# 12V_Supply.net
KiCad netlist of a schematic drawn in Altium Designer
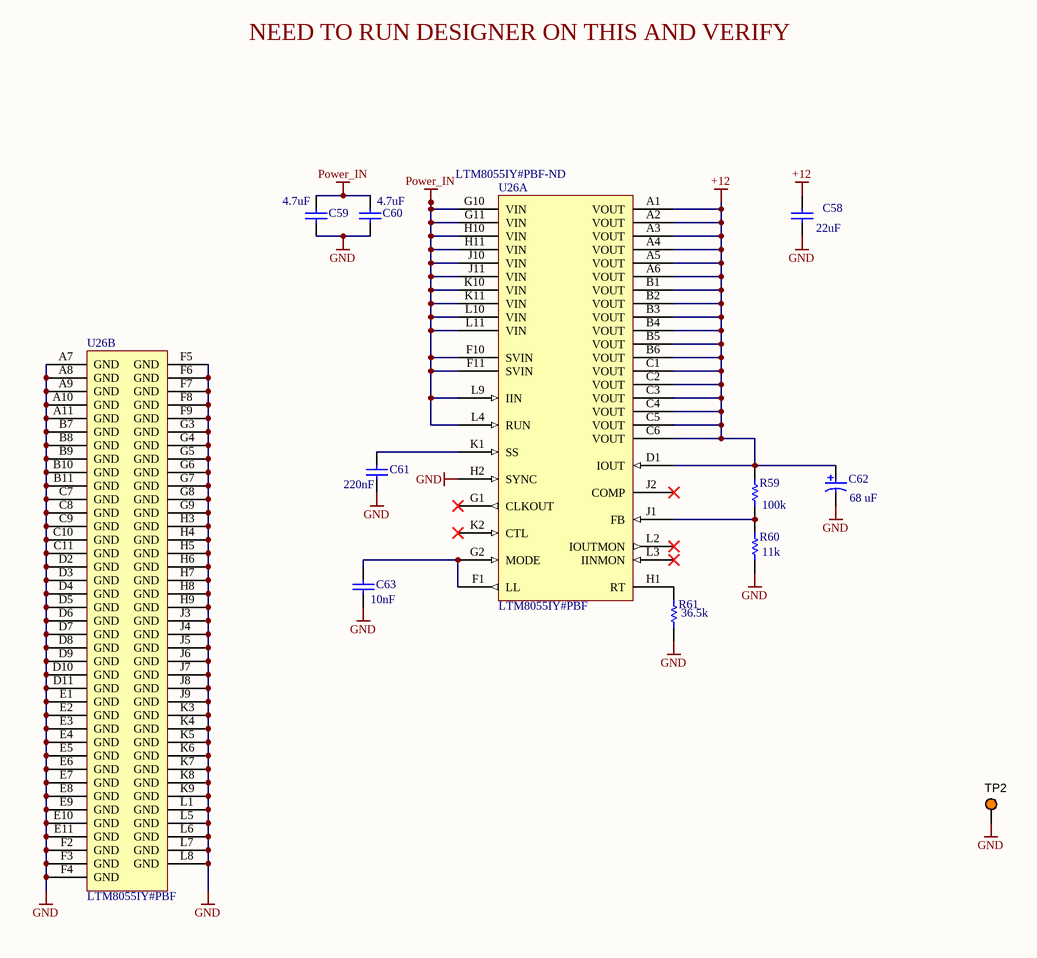
[diagram p0: 12V_Supply.SchDoc]

(export (version "E")
  (design (tool "Eeschema 10.0.6"))
  (components
    (comp (ref "C58")
      (value "CAP CER 1UF 25V X7R 0805")
      (footprint "CAPC0805(2012)155_L")
      (description "22uF 25V X7R 20% 0805")
      (fields
        (field (name "CAPACITANCE") "22uF")
        (field (name "MANUFACTURER") "Kyocera AVX")
        (field (name "MANUFACTURER PART NUMBER") "08053C105JAT2A")
      )
      (libsource (lib "Altium Content Vault") (part "CMP-1036-04882-1"))
    )
    (comp (ref "C59")
      (value "C1210C475K5RACTU")
      (footprint "CAPC3225X280X50LL20T25")
      (description "Chip Capacitor, 4.7 uF, +/- 10%, 50 V, -55 to 125 degC, 1210 (3225 Metric), RoHS, Tape and Reel")
      (fields
        (field (name "VOLTAGE") "50V")
        (field (name "MANUFACTURER") "Kemet")
        (field (name "CAPACITANCE") "4.7uF")
      )
      (libsource (lib "Altium Content Vault") (part "CMP-2000-07550-1"))
    )
    (comp (ref "C60")
      (value "C1210C475K5RACTU")
      (footprint "CAPC3225X280X50LL20T25")
      (description "Chip Capacitor, 4.7 uF, +/- 10%, 50 V, -55 to 125 degC, 1210 (3225 Metric), RoHS, Tape and Reel")
      (fields
        (field (name "VOLTAGE") "50V")
        (field (name "MANUFACTURER") "Kemet")
        (field (name "CAPACITANCE") "4.7uF")
      )
      (libsource (lib "Altium Content Vault") (part "CMP-2000-07550-1"))
    )
    (comp (ref "C61")
      (value "GRM155R71C224KA12D")
      (footprint "CAPC0402(1005)60_M")
      (description "0.22µF ±10% 16V Ceramic Capacitor X7R 0402 (1005 Metric)")
      (fields
        (field (name "TOLERANCE") "Â±10%")
        (field (name "MANUFACTURER") "Murata")
        (field (name "CAPACITANCE") "220nF")
      )
      (libsource (lib "Altium Content Vault") (part "CAP"))
    )
    (comp (ref "C62")
      (value "UUD1E680MCL1GS")
      (footprint "NIC-CAPA2-6.3X5.8_V")
      (fields (field (name "RATED CAPACITANCE") "68 uF") (field (name "MANUFACTURER") "Nichicon"))
      (libsource (lib "Altium Content Vault") (part "NIC-CAP-P-2"))
    )
    (comp (ref "C63")
      (value "0402YC103KAT2A")
      (footprint "CAPC1005X56X25NL10T15")
      (description "10000pF ±10% 16V Ceramic Capacitor X7R 0402 (1005 Metric)")
      (fields
        (field (name "MANUFACTURER") "AVX Interconnect / Elco")
        (field (name "CAPACITANCE") "10nF")
        (field (name "TOLERANCE") "10%")
      )
      (libsource (lib "Altium Content Vault") (part "CAP"))
    )
    (comp (ref "R59")
      (value "CRCW0603100KFKEA")
      (footprint "RESC1609X50X30LL10T20")
      (description "100 kOhms ±1% 0.1W, 1/10W Chip Resistor 0603 (1608 Metric) Automotive AEC-Q200 Thick Film")
      (fields
        (field (name "MANUFACTURER") "Vishay Dale")
        (field (name "MANUFACTURER PART NUMBER") "CRCW0603-100KFKEA")
        (field (name "RESISTANCE") "100k")
      )
      (libsource (lib "Altium Content Vault") (part "RES"))
    )
    (comp (ref "R60")
      (value "CRCW060311K0FKEA")
      (footprint "RESC1609X50X30ML10T20")
      (description "11 kOhms ±1% 0.1W, 1/10W Chip Resistor 0603 (1608 Metric) Automotive AEC-Q200 Thick Film")
      (fields
        (field (name "MANUFACTURER") "Vishay Dale")
        (field (name "RESISTANCE") "11k")
        (field (name "TOLERANCE") "1%")
      )
      (libsource (lib "Altium Content Vault") (part "RES"))
    )
    (comp (ref "R61")
      (value "CRCW080536K5FKEA")
      (footprint "RESC0805(2012)_L")
      (description "36.5 kOhms ±1% 0.125W, 1/8W Chip Resistor 0805 (2012 Metric) Automotive AEC-Q200 Thick Film")
      (fields
        (field (name "POWER") "0.125 W")
        (field (name "TOLERANCE") "1 %")
        (field (name "RESISTANCE") "36.5k")
      )
      (libsource (lib "Altium Content Vault") (part "RES"))
    )
    (comp (ref "TP2")
      (value "5003")
      (footprint "KSTN-5003")
      (description "Test Point, Orange, 1-Pin THD, RoHS")
      (libsource (lib "Altium Content Vault") (part "CMP-1672-00009-1"))
    )
    (comp (ref "U26")
      (value "LTM8055IY#PBF")
      (footprint "LT-BGA-121-15000X15000X4920")
      (description "Buck-Boost uModule Regulator, 8.5 A, 5 to 36 V, -40 to 125 degC, 121-Ball BGA, RoHS, Tray")
      (fields
        (field (name "MANUFACTURER") "LinearTechnology")
        (field (name "SUPPLIER PART NUMBER 1") "LTM8055IY#PBF-ND")
      )
      (libsource (lib "Altium Content Vault") (part "LT-LTM8055-BGA-121"))
    )
  )
  (nets
    (net (code "1") (name "+12") (class "Default")
      (node (ref "C58") (pin "2") (pinfunction "2_2") (pintype "passive"))
      (node (ref "C62") (pin "1") (pinfunction "1_1") (pintype "passive"))
      (node (ref "R59") (pin "2") (pinfunction "2_2") (pintype "passive"))
      (node (ref "U26") (pin "A1") (pinfunction "VOUT_A1") (pintype "power_in"))
      (node (ref "U26") (pin "A2") (pinfunction "VOUT_A2") (pintype "power_in"))
      (node (ref "U26") (pin "A3") (pinfunction "VOUT_A3") (pintype "power_in"))
      (node (ref "U26") (pin "A4") (pinfunction "VOUT_A4") (pintype "power_in"))
      (node (ref "U26") (pin "A5") (pinfunction "VOUT_A5") (pintype "power_in"))
      (node (ref "U26") (pin "A6") (pinfunction "VOUT_A6") (pintype "power_in"))
      (node (ref "U26") (pin "B1") (pinfunction "VOUT_B1") (pintype "power_in"))
      (node (ref "U26") (pin "B2") (pinfunction "VOUT_B2") (pintype "power_in"))
      (node (ref "U26") (pin "B3") (pinfunction "VOUT_B3") (pintype "power_in"))
      (node (ref "U26") (pin "B4") (pinfunction "VOUT_B4") (pintype "power_in"))
      (node (ref "U26") (pin "B5") (pinfunction "VOUT_B5") (pintype "power_in"))
      (node (ref "U26") (pin "B6") (pinfunction "VOUT_B6") (pintype "power_in"))
      (node (ref "U26") (pin "C1") (pinfunction "VOUT_C1") (pintype "power_in"))
      (node (ref "U26") (pin "C2") (pinfunction "VOUT_C2") (pintype "power_in"))
      (node (ref "U26") (pin "C3") (pinfunction "VOUT_C3") (pintype "power_in"))
      (node (ref "U26") (pin "C4") (pinfunction "VOUT_C4") (pintype "power_in"))
      (node (ref "U26") (pin "C5") (pinfunction "VOUT_C5") (pintype "power_in"))
      (node (ref "U26") (pin "C6") (pinfunction "VOUT_C6") (pintype "power_in"))
      (node (ref "U26") (pin "D1") (pinfunction "IOUT_D1") (pintype "input"))
    )
    (net (code "2") (name "GND") (class "Default")
      (node (ref "C58") (pin "1") (pinfunction "1_1") (pintype "passive"))
      (node (ref "C59") (pin "1") (pinfunction "1_1") (pintype "passive"))
      (node (ref "C60") (pin "1") (pinfunction "1_1") (pintype "passive"))
      (node (ref "C61") (pin "1") (pinfunction "1_1") (pintype "passive"))
      (node (ref "C62") (pin "2") (pinfunction "2_2") (pintype "passive"))
      (node (ref "C63") (pin "1") (pinfunction "1_1") (pintype "passive"))
      (node (ref "R60") (pin "1") (pinfunction "1_1") (pintype "passive"))
      (node (ref "R61") (pin "1") (pinfunction "1_1") (pintype "passive"))
      (node (ref "TP2") (pin "1") (pinfunction "1_1") (pintype "passive"))
      (node (ref "U26") (pin "A10") (pinfunction "GND_A10") (pintype "power_in"))
      (node (ref "U26") (pin "A11") (pinfunction "GND_A11") (pintype "power_in"))
      (node (ref "U26") (pin "A7") (pinfunction "GND_A7") (pintype "power_in"))
      (node (ref "U26") (pin "A8") (pinfunction "GND_A8") (pintype "power_in"))
      (node (ref "U26") (pin "A9") (pinfunction "GND_A9") (pintype "power_in"))
      (node (ref "U26") (pin "B10") (pinfunction "GND_B10") (pintype "power_in"))
      (node (ref "U26") (pin "B11") (pinfunction "GND_B11") (pintype "power_in"))
      (node (ref "U26") (pin "B7") (pinfunction "GND_B7") (pintype "power_in"))
      (node (ref "U26") (pin "B8") (pinfunction "GND_B8") (pintype "power_in"))
      (node (ref "U26") (pin "B9") (pinfunction "GND_B9") (pintype "power_in"))
      (node (ref "U26") (pin "C10") (pinfunction "GND_C10") (pintype "power_in"))
      (node (ref "U26") (pin "C11") (pinfunction "GND_C11") (pintype "power_in"))
      (node (ref "U26") (pin "C7") (pinfunction "GND_C7") (pintype "power_in"))
      (node (ref "U26") (pin "C8") (pinfunction "GND_C8") (pintype "power_in"))
      (node (ref "U26") (pin "C9") (pinfunction "GND_C9") (pintype "power_in"))
      (node (ref "U26") (pin "D10") (pinfunction "GND_D10") (pintype "power_in"))
      (node (ref "U26") (pin "D11") (pinfunction "GND_D11") (pintype "power_in"))
      (node (ref "U26") (pin "D2") (pinfunction "GND_D2") (pintype "power_in"))
      (node (ref "U26") (pin "D3") (pinfunction "GND_D3") (pintype "power_in"))
      (node (ref "U26") (pin "D4") (pinfunction "GND_D4") (pintype "power_in"))
      (node (ref "U26") (pin "D5") (pinfunction "GND_D5") (pintype "power_in"))
      (node (ref "U26") (pin "D6") (pinfunction "GND_D6") (pintype "power_in"))
      (node (ref "U26") (pin "D7") (pinfunction "GND_D7") (pintype "power_in"))
      (node (ref "U26") (pin "D8") (pinfunction "GND_D8") (pintype "power_in"))
      (node (ref "U26") (pin "D9") (pinfunction "GND_D9") (pintype "power_in"))
      (node (ref "U26") (pin "E1") (pinfunction "GND_E1") (pintype "power_in"))
      (node (ref "U26") (pin "E10") (pinfunction "GND_E10") (pintype "power_in"))
      (node (ref "U26") (pin "E11") (pinfunction "GND_E11") (pintype "power_in"))
      (node (ref "U26") (pin "E2") (pinfunction "GND_E2") (pintype "power_in"))
      (node (ref "U26") (pin "E3") (pinfunction "GND_E3") (pintype "power_in"))
      (node (ref "U26") (pin "E4") (pinfunction "GND_E4") (pintype "power_in"))
      (node (ref "U26") (pin "E5") (pinfunction "GND_E5") (pintype "power_in"))
      (node (ref "U26") (pin "E6") (pinfunction "GND_E6") (pintype "power_in"))
      (node (ref "U26") (pin "E7") (pinfunction "GND_E7") (pintype "power_in"))
      (node (ref "U26") (pin "E8") (pinfunction "GND_E8") (pintype "power_in"))
      (node (ref "U26") (pin "E9") (pinfunction "GND_E9") (pintype "power_in"))
      (node (ref "U26") (pin "F2") (pinfunction "GND_F2") (pintype "power_in"))
      (node (ref "U26") (pin "F3") (pinfunction "GND_F3") (pintype "power_in"))
      (node (ref "U26") (pin "F4") (pinfunction "GND_F4") (pintype "power_in"))
      (node (ref "U26") (pin "F5") (pinfunction "GND_F5") (pintype "power_in"))
      (node (ref "U26") (pin "F6") (pinfunction "GND_F6") (pintype "power_in"))
      (node (ref "U26") (pin "F7") (pinfunction "GND_F7") (pintype "power_in"))
      (node (ref "U26") (pin "F8") (pinfunction "GND_F8") (pintype "power_in"))
      (node (ref "U26") (pin "F9") (pinfunction "GND_F9") (pintype "power_in"))
      (node (ref "U26") (pin "G3") (pinfunction "GND_G3") (pintype "power_in"))
      (node (ref "U26") (pin "G4") (pinfunction "GND_G4") (pintype "power_in"))
      (node (ref "U26") (pin "G5") (pinfunction "GND_G5") (pintype "power_in"))
      (node (ref "U26") (pin "G6") (pinfunction "GND_G6") (pintype "power_in"))
      (node (ref "U26") (pin "G7") (pinfunction "GND_G7") (pintype "power_in"))
      (node (ref "U26") (pin "G8") (pinfunction "GND_G8") (pintype "power_in"))
      (node (ref "U26") (pin "G9") (pinfunction "GND_G9") (pintype "power_in"))
      (node (ref "U26") (pin "H2") (pinfunction "SYNC_H2") (pintype "input"))
      (node (ref "U26") (pin "H3") (pinfunction "GND_H3") (pintype "power_in"))
      (node (ref "U26") (pin "H4") (pinfunction "GND_H4") (pintype "power_in"))
      (node (ref "U26") (pin "H5") (pinfunction "GND_H5") (pintype "power_in"))
      (node (ref "U26") (pin "H6") (pinfunction "GND_H6") (pintype "power_in"))
      (node (ref "U26") (pin "H7") (pinfunction "GND_H7") (pintype "power_in"))
      (node (ref "U26") (pin "H8") (pinfunction "GND_H8") (pintype "power_in"))
      (node (ref "U26") (pin "H9") (pinfunction "GND_H9") (pintype "power_in"))
      (node (ref "U26") (pin "J3") (pinfunction "GND_J3") (pintype "power_in"))
      (node (ref "U26") (pin "J4") (pinfunction "GND_J4") (pintype "power_in"))
      (node (ref "U26") (pin "J5") (pinfunction "GND_J5") (pintype "power_in"))
      (node (ref "U26") (pin "J6") (pinfunction "GND_J6") (pintype "power_in"))
      (node (ref "U26") (pin "J7") (pinfunction "GND_J7") (pintype "power_in"))
      (node (ref "U26") (pin "J8") (pinfunction "GND_J8") (pintype "power_in"))
      (node (ref "U26") (pin "J9") (pinfunction "GND_J9") (pintype "power_in"))
      (node (ref "U26") (pin "K3") (pinfunction "GND_K3") (pintype "power_in"))
      (node (ref "U26") (pin "K4") (pinfunction "GND_K4") (pintype "power_in"))
      (node (ref "U26") (pin "K5") (pinfunction "GND_K5") (pintype "power_in"))
      (node (ref "U26") (pin "K6") (pinfunction "GND_K6") (pintype "power_in"))
      (node (ref "U26") (pin "K7") (pinfunction "GND_K7") (pintype "power_in"))
      (node (ref "U26") (pin "K8") (pinfunction "GND_K8") (pintype "power_in"))
      (node (ref "U26") (pin "K9") (pinfunction "GND_K9") (pintype "power_in"))
      (node (ref "U26") (pin "L1") (pinfunction "GND_L1") (pintype "power_in"))
      (node (ref "U26") (pin "L5") (pinfunction "GND_L5") (pintype "power_in"))
      (node (ref "U26") (pin "L6") (pinfunction "GND_L6") (pintype "power_in"))
      (node (ref "U26") (pin "L7") (pinfunction "GND_L7") (pintype "power_in"))
      (node (ref "U26") (pin "L8") (pinfunction "GND_L8") (pintype "power_in"))
    )
    (net (code "3") (name "Net-(U26A-FB)") (class "Default")
      (node (ref "R59") (pin "1") (pinfunction "1_1") (pintype "passive"))
      (node (ref "R60") (pin "2") (pinfunction "2_2") (pintype "passive"))
      (node (ref "U26") (pin "J1") (pinfunction "FB_J1") (pintype "input"))
    )
    (net (code "4") (name "Net-(U26A-LL)") (class "Default")
      (node (ref "C63") (pin "2") (pinfunction "2_2") (pintype "passive"))
      (node (ref "U26") (pin "F1") (pinfunction "LL_F1") (pintype "output"))
      (node (ref "U26") (pin "G2") (pinfunction "MODE_G2") (pintype "input"))
    )
    (net (code "5") (name "Net-(U26A-RT)") (class "Default")
      (node (ref "R61") (pin "2") (pinfunction "2_2") (pintype "passive"))
      (node (ref "U26") (pin "H1") (pinfunction "RT_H1") (pintype "passive"))
    )
    (net (code "6") (name "Net-(U26A-SS)") (class "Default")
      (node (ref "C61") (pin "2") (pinfunction "2_2") (pintype "passive"))
      (node (ref "U26") (pin "K1") (pinfunction "SS_K1") (pintype "input"))
    )
    (net (code "7") (name "Power_IN") (class "Default")
      (node (ref "C59") (pin "2") (pinfunction "2_2") (pintype "passive"))
      (node (ref "C60") (pin "2") (pinfunction "2_2") (pintype "passive"))
      (node (ref "U26") (pin "F10") (pinfunction "SVIN_F10") (pintype "power_in"))
      (node (ref "U26") (pin "F11") (pinfunction "SVIN_F11") (pintype "power_in"))
      (node (ref "U26") (pin "G10") (pinfunction "VIN_G10") (pintype "power_in"))
      (node (ref "U26") (pin "G11") (pinfunction "VIN_G11") (pintype "power_in"))
      (node (ref "U26") (pin "H10") (pinfunction "VIN_H10") (pintype "power_in"))
      (node (ref "U26") (pin "H11") (pinfunction "VIN_H11") (pintype "power_in"))
      (node (ref "U26") (pin "J10") (pinfunction "VIN_J10") (pintype "power_in"))
      (node (ref "U26") (pin "J11") (pinfunction "VIN_J11") (pintype "power_in"))
      (node (ref "U26") (pin "K10") (pinfunction "VIN_K10") (pintype "power_in"))
      (node (ref "U26") (pin "K11") (pinfunction "VIN_K11") (pintype "power_in"))
      (node (ref "U26") (pin "L10") (pinfunction "VIN_L10") (pintype "power_in"))
      (node (ref "U26") (pin "L11") (pinfunction "VIN_L11") (pintype "power_in"))
      (node (ref "U26") (pin "L4") (pinfunction "RUN_L4") (pintype "input"))
      (node (ref "U26") (pin "L9") (pinfunction "IIN_L9") (pintype "input"))
    )
    (net (code "8") (name "unconnected-(U26A-CLKOUT-PadG1)") (class "Default")
      (node (ref "U26") (pin "G1") (pinfunction "CLKOUT_G1") (pintype "output+no_connect"))
    )
    (net (code "9") (name "unconnected-(U26A-COMP-PadJ2)") (class "Default")
      (node (ref "U26") (pin "J2") (pinfunction "COMP_J2") (pintype "passive+no_connect"))
    )
    (net (code "10") (name "unconnected-(U26A-CTL-PadK2)") (class "Default")
      (node (ref "U26") (pin "K2") (pinfunction "CTL_K2") (pintype "input+no_connect"))
    )
    (net (code "11") (name "unconnected-(U26A-IINMON-PadL3)") (class "Default")
      (node (ref "U26") (pin "L3") (pinfunction "IINMON_L3") (pintype "input+no_connect"))
    )
    (net (code "12") (name "unconnected-(U26A-IOUTMON-PadL2)") (class "Default")
      (node (ref "U26") (pin "L2") (pinfunction "IOUTMON_L2") (pintype "output+no_connect"))
    )
  )
)
